# spi_loopback_b.net
KiCad netlist of a schematic drawn in Altium Designer
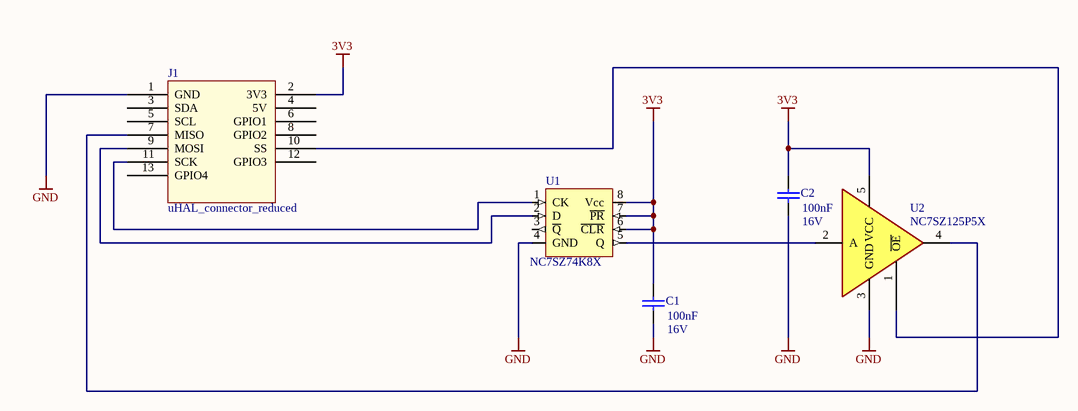
[diagram p0: spi_loopback_b.SchDoc]

(export (version "E")
  (design (tool "Eeschema 10.0.6"))
  (components
    (comp (ref "C1")
      (value "Kemet C0603C104K4RAC7013")
      (footprint "CAPC1608X90X35NL15T15")
      (description "CAP CER 0.1UF 16V 10% X7R 0603")
      (fields (field (name "CAPACITANCE") "100nF") (field (name "VOLTAGE RATING (DC)") "16V"))
      (libsource (lib "CommunityVault") (part "CMP-4113029-2"))
    )
    (comp (ref "C2")
      (value "Kemet C0603C104K4RAC7013")
      (footprint "CAPC1608X90X35NL15T15")
      (description "CAP CER 0.1UF 16V 10% X7R 0603")
      (fields (field (name "CAPACITANCE") "100nF") (field (name "VOLTAGE RATING (DC)") "16V"))
      (libsource (lib "CommunityVault") (part "CMP-4113029-2"))
    )
    (comp (ref "J1")
      (value "uHAL_connector_reduced")
      (footprint "PCB-45ncoppm4oopozvqifsq-1")
      (description "connector for uHAL with reduced pin number")
      (libsource (lib "CommunityVault") (part "CMP-2q23h2cwhjlfm8s6r7i8-1"))
    )
    (comp (ref "U1")
      (value "ON Semiconductor NC7SZ74K8X")
      (footprint "SOP8")
      (description "NC7SZ74 Series 5.5 V TinyLogic UHS D-Type Flip-Flop with Preset and Clear - US8")
      (fields (field (name "MANUFACTURER PART NUMBER") "NC7SZ74K8X"))
      (libsource (lib "CommunityVault") (part "CMP-a3886f844fd47c4f-2"))
    )
    (comp (ref "U2")
      (value "NC7SZ125P5X")
      (footprint "SOT23127P600-8N")
      (description "NC7SZ125 Series 5.5 V TinyLogic® UHS Single Buffer w/ 3-State Output - SC-70-5")
      (fields (field (name "MANUFACTURER PART NUMBER") "NC7SZ125P5X"))
      (libsource (lib "CommunityVault") (part "CMP-f54f3c43aefd2a88-2"))
    )
  )
  (nets
    (net (code "1") (name "3V3") (class "Default")
      (node (ref "C1") (pin "2") (pinfunction "2_2") (pintype "passive"))
      (node (ref "C2") (pin "2") (pinfunction "2_2") (pintype "passive"))
      (node (ref "J1") (pin "2") (pinfunction "3V3_2") (pintype "passive"))
      (node (ref "U1") (pin "6") (pinfunction "~{CLR}_6") (pintype "input"))
      (node (ref "U1") (pin "7") (pinfunction "~{PR}_7") (pintype "input"))
      (node (ref "U1") (pin "8") (pinfunction "Vcc_8") (pintype "power_in"))
      (node (ref "U2") (pin "5") (pinfunction "VCC_5") (pintype "passive"))
    )
    (net (code "2") (name "GND") (class "Default")
      (node (ref "C1") (pin "1") (pinfunction "1_1") (pintype "passive"))
      (node (ref "C2") (pin "1") (pinfunction "1_1") (pintype "passive"))
      (node (ref "J1") (pin "1") (pinfunction "GND_1") (pintype "passive"))
      (node (ref "U1") (pin "4") (pinfunction "GND_4") (pintype "power_in"))
      (node (ref "U2") (pin "3") (pinfunction "GND_3") (pintype "passive"))
    )
    (net (code "3") (name "Net-(J1-MISO)") (class "Default")
      (node (ref "J1") (pin "7") (pinfunction "MISO_7") (pintype "passive"))
      (node (ref "U2") (pin "4") (pinfunction "Y_4") (pintype "passive"))
    )
    (net (code "4") (name "Net-(J1-MOSI)") (class "Default")
      (node (ref "J1") (pin "9") (pinfunction "MOSI_9") (pintype "passive"))
      (node (ref "U1") (pin "2") (pinfunction "D_2") (pintype "input"))
    )
    (net (code "5") (name "Net-(J1-SCK)") (class "Default")
      (node (ref "J1") (pin "11") (pinfunction "SCK_11") (pintype "passive"))
      (node (ref "U1") (pin "1") (pinfunction "CK_1") (pintype "input"))
    )
    (net (code "6") (name "Net-(J1-SS)") (class "Default")
      (node (ref "J1") (pin "10") (pinfunction "SS_10") (pintype "passive"))
      (node (ref "U2") (pin "1") (pinfunction "~{OE}_1") (pintype "passive"))
    )
    (net (code "7") (name "Net-(U1-Q)") (class "Default")
      (node (ref "U1") (pin "5") (pinfunction "Q_5") (pintype "output"))
      (node (ref "U2") (pin "2") (pinfunction "A_2") (pintype "passive"))
    )
    (net (code "8") (name "unconnected-(J1-5V-Pad4)") (class "Default")
      (node (ref "J1") (pin "4") (pinfunction "5V_4") (pintype "passive"))
    )
    (net (code "9") (name "unconnected-(J1-GPIO1-Pad6)") (class "Default")
      (node (ref "J1") (pin "6") (pinfunction "GPIO1_6") (pintype "passive"))
    )
    (net (code "10") (name "unconnected-(J1-GPIO2-Pad8)") (class "Default")
      (node (ref "J1") (pin "8") (pinfunction "GPIO2_8") (pintype "passive"))
    )
    (net (code "11") (name "unconnected-(J1-GPIO3-Pad12)") (class "Default")
      (node (ref "J1") (pin "12") (pinfunction "GPIO3_12") (pintype "passive"))
    )
    (net (code "12") (name "unconnected-(J1-GPIO4-Pad13)") (class "Default")
      (node (ref "J1") (pin "13") (pinfunction "GPIO4_13") (pintype "passive"))
    )
    (net (code "13") (name "unconnected-(J1-SCL-Pad5)") (class "Default")
      (node (ref "J1") (pin "5") (pinfunction "SCL_5") (pintype "passive"))
    )
    (net (code "14") (name "unconnected-(J1-SDA-Pad3)") (class "Default")
      (node (ref "J1") (pin "3") (pinfunction "SDA_3") (pintype "passive"))
    )
    (net (code "15") (name "unconnected-(U1-~{Q}-Pad3)") (class "Default")
      (node (ref "U1") (pin "3") (pinfunction "~{Q}_3") (pintype "output"))
    )
  )
)
